# tPen.net
KiCad netlist of a schematic drawn in Altium Designer
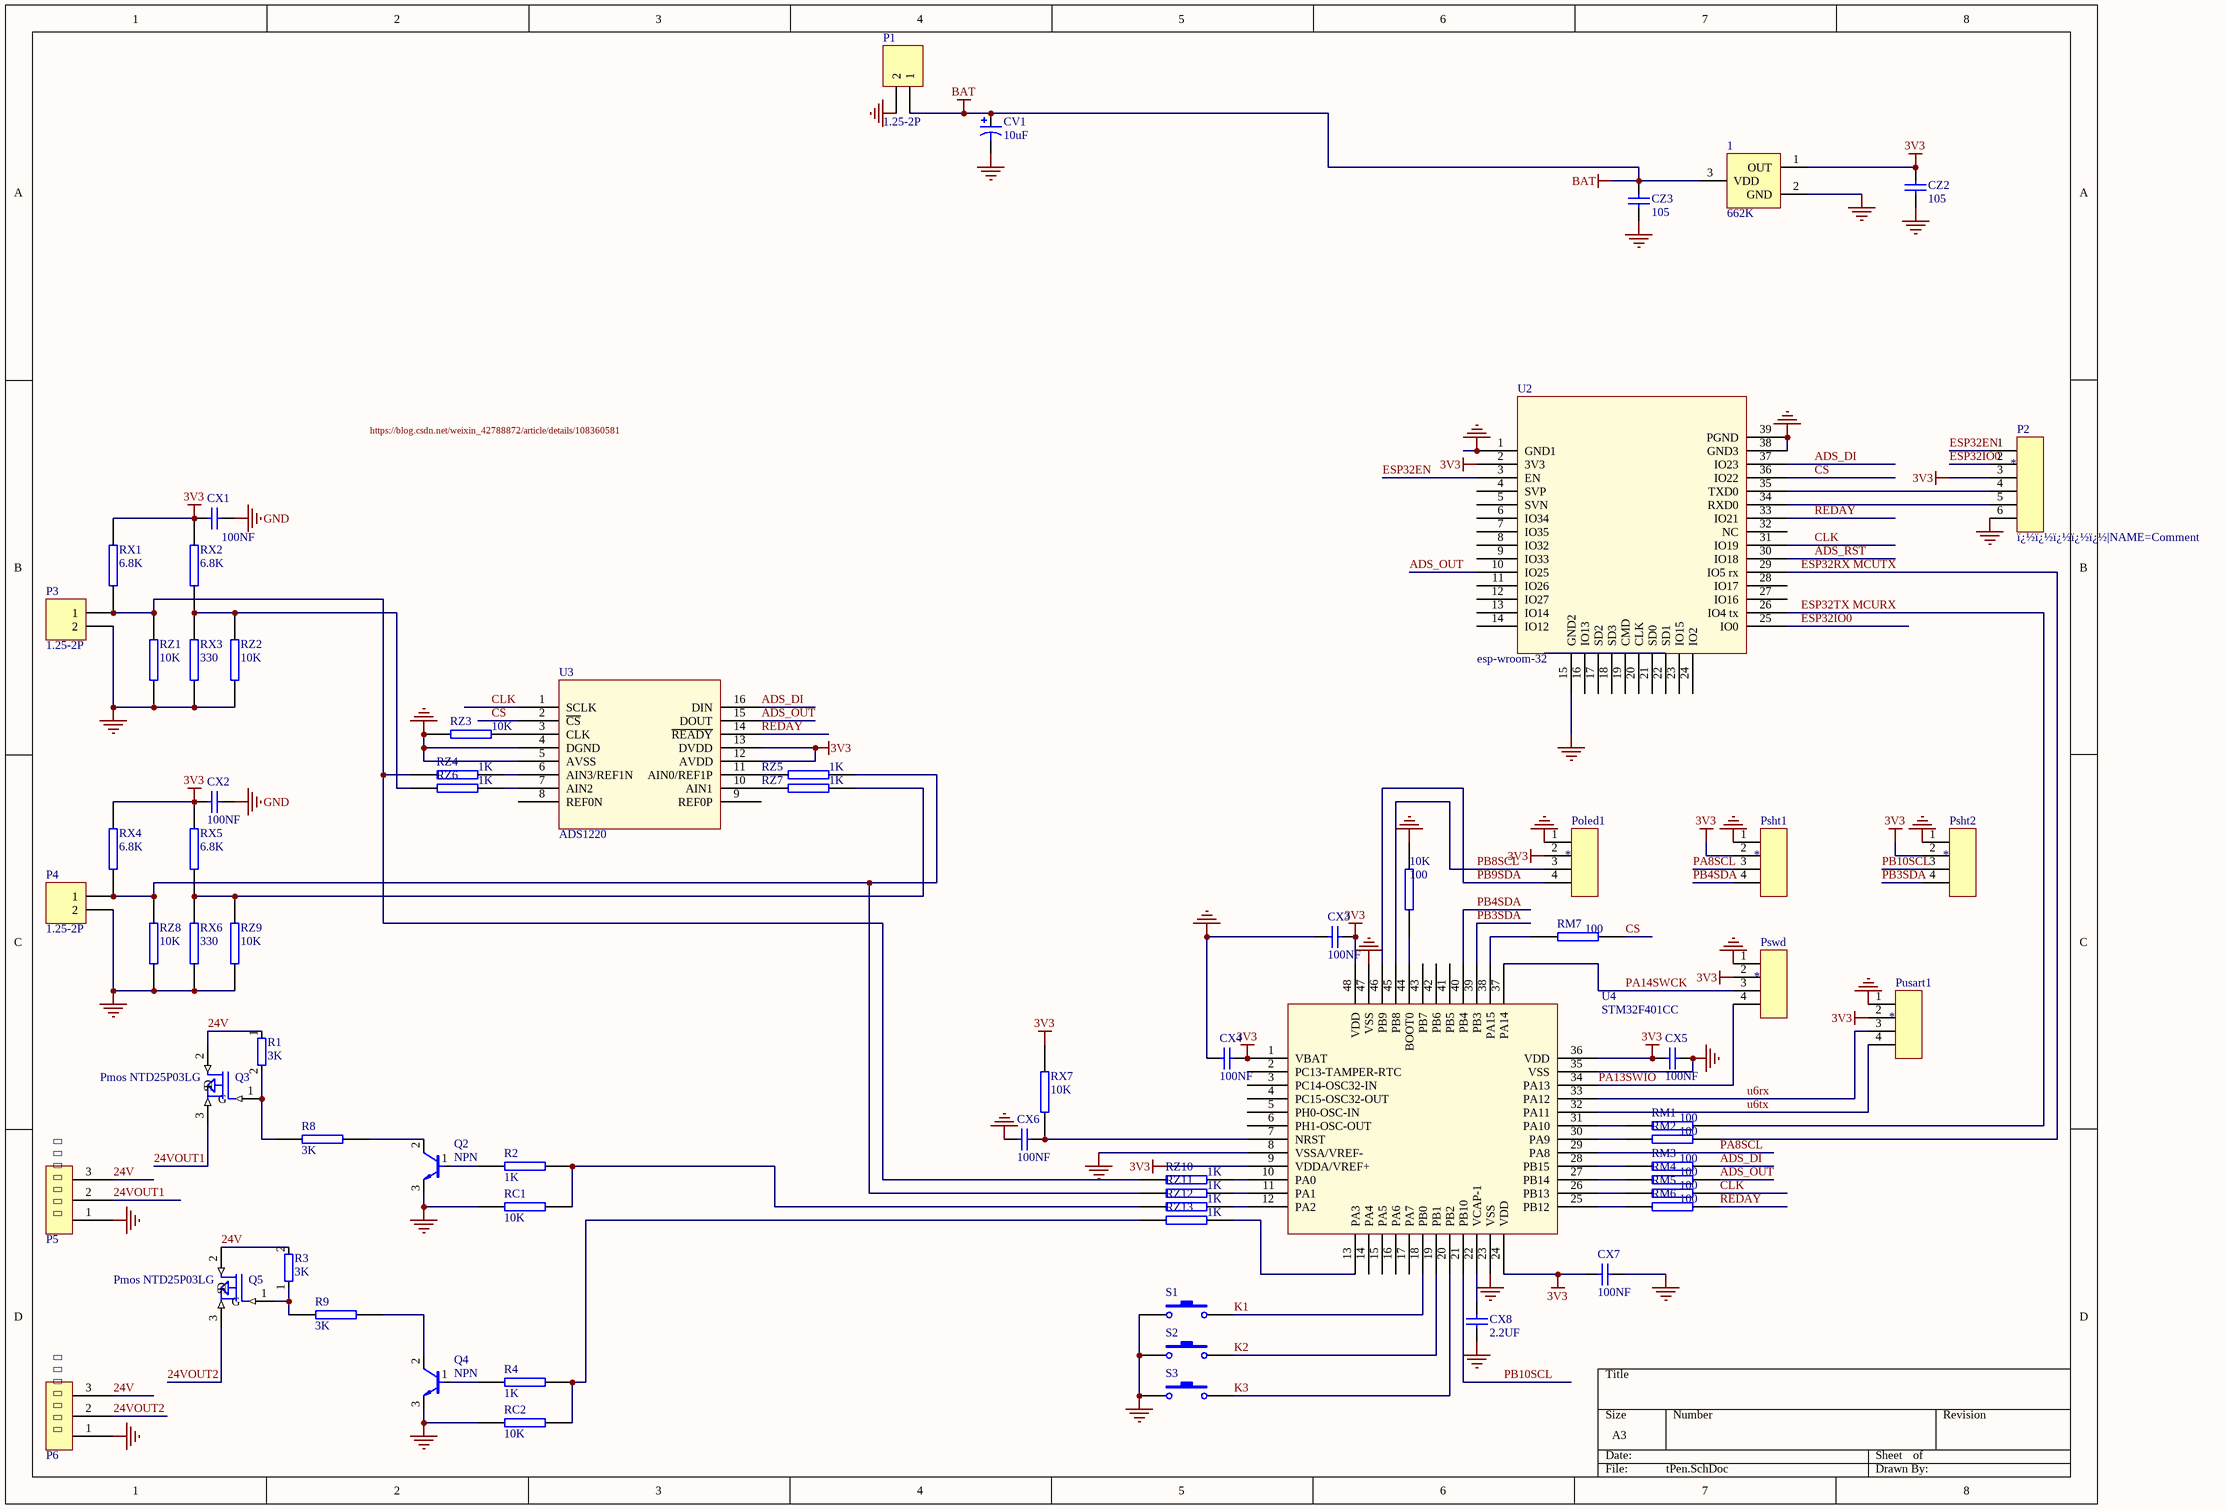
[diagram p0: tPen.SchDoc]

(export (version "E")
  (design (tool "Eeschema 10.0.6"))
  (components
    (comp (ref "1")
      (value "662K")
      (footprint "SOT23-3-1")
      (libsource (lib "SCHÔ­ï¿½ï¿½Í¼ï¿½ï¿½") (part "MH5330"))
    )
    (comp (ref "10K") (value "100") (footprint "0603") (libsource (lib "*") (part "RES2")))
    (comp (ref "CV1")
      (value "10uF")
      (footprint "0603")
      (description "Polarized Capacitor (Radial)")
      (libsource (lib "Miscellaneous Devices") (part "Cap Pol1"))
    )
    (comp (ref "CX1")
      (value "100NF")
      (footprint "0603")
      (description "Capacitor")
      (libsource (lib "Ô­ï¿½ï¿½Í¼ï¿½ï¿½") (part "104"))
    )
    (comp (ref "CX2")
      (value "100NF")
      (footprint "0603")
      (description "Capacitor")
      (libsource (lib "Ô­ï¿½ï¿½Í¼ï¿½ï¿½") (part "104"))
    )
    (comp (ref "CX3")
      (value "100NF")
      (footprint "0603")
      (description "Capacitor")
      (libsource (lib "Ô­ï¿½ï¿½Í¼ï¿½ï¿½") (part "104"))
    )
    (comp (ref "CX4")
      (value "100NF")
      (footprint "0603")
      (description "Capacitor")
      (libsource (lib "Ô­ï¿½ï¿½Í¼ï¿½ï¿½") (part "104"))
    )
    (comp (ref "CX5")
      (value "100NF")
      (footprint "0603")
      (description "Capacitor")
      (libsource (lib "Ô­ï¿½ï¿½Í¼ï¿½ï¿½") (part "104"))
    )
    (comp (ref "CX6")
      (value "100NF")
      (footprint "0603")
      (description "Capacitor")
      (libsource (lib "Ô­ï¿½ï¿½Í¼ï¿½ï¿½") (part "104"))
    )
    (comp (ref "CX7")
      (value "100NF")
      (footprint "0603")
      (description "Capacitor")
      (libsource (lib "Ô­ï¿½ï¿½Í¼ï¿½ï¿½") (part "104"))
    )
    (comp (ref "CX8")
      (value "2.2UF")
      (footprint "0603")
      (description "Capacitor")
      (libsource (lib "Ô­ï¿½ï¿½Í¼ï¿½ï¿½") (part "104"))
    )
    (comp (ref "CZ2")
      (value "105")
      (footprint "0603")
      (description "Capacitor")
      (libsource (lib "Ô­ï¿½ï¿½Í¼ï¿½ï¿½") (part "104"))
    )
    (comp (ref "CZ3")
      (value "105")
      (footprint "0603")
      (description "Capacitor")
      (libsource (lib "Ô­ï¿½ï¿½Í¼ï¿½ï¿½") (part "104"))
    )
    (comp (ref "P1")
      (value "1.25-2P")
      (footprint "1.25ï¿½ï¿½ï¿½ï¿½-ï¿½ï¿½Ê½Í¨ï¿½ï¿½-2P")
      (description "Header, 2-Pin")
      (fields (field (name "PUBLISHER") "Altium Limited"))
      (libsource (lib "") (part "Header 2_1"))
    )
    (comp (ref "P2")
      (value "*")
      (footprint "B6B-XH-A")
      (fields (field (name "ALTIUM_UNNAMED_1") "ï¿½ï¿½ï¿½ï¿½ï¿½NAME=Comment"))
      (libsource (lib "") (part "ï¿½Ó²ï¿½ï¿½ï¿½ï¿?P_1"))
    )
    (comp (ref "P3")
      (value "1.25-2P")
      (footprint "1.25ï¿½ï¿½ï¿½ï¿½-ï¿½ï¿½Ê½Í¨ï¿½ï¿½-2P")
      (description "Header, 2-Pin")
      (fields (field (name "PUBLISHER") "Altium Limited"))
      (libsource (lib "SCHÔ­ï¿½ï¿½Í¼ï¿½ï¿½") (part "Header 2"))
    )
    (comp (ref "P4")
      (value "1.25-2P")
      (footprint "1.25ï¿½ï¿½ï¿½ï¿½-ï¿½ï¿½Ê½Í¨ï¿½ï¿½-2P")
      (description "Header, 2-Pin")
      (fields (field (name "PUBLISHER") "Altium Limited"))
      (libsource (lib "SCHÔ­ï¿½ï¿½Í¼ï¿½ï¿½") (part "Header 2"))
    )
    (comp (ref "P5")
      (value "3Pï¿½ï¿½ï¿½ß¶ï¿½ï¿½ï¿½")
      (footprint "XH2.54-3")
      (libsource (lib "ï¿½Ó²ï¿½ï¿½Ôªï¿½ï¿½ï¿½ï¿?SchLib") (part "3Pï¿½ï¿½ï¿½ß¶ï¿½ï¿½ï¿½"))
    )
    (comp (ref "P6")
      (value "3Pï¿½ï¿½ï¿½ß¶ï¿½ï¿½ï¿½")
      (footprint "XH2.54-3")
      (libsource (lib "ï¿½Ó²ï¿½ï¿½Ôªï¿½ï¿½ï¿½ï¿?SchLib") (part "3Pï¿½ï¿½ï¿½ß¶ï¿½ï¿½ï¿½"))
    )
    (comp (ref "Poled1")
      (value "*")
      (footprint "0.96OLED")
      (libsource (lib "ï¿½Ó²ï¿½ï¿½Ôªï¿½ï¿½ï¿½ï¿?SchLib") (part "ï¿½Ó²ï¿½ï¿½ï¿½ï¿?P"))
    )
    (comp (ref "Psht1")
      (value "*")
      (footprint "B4B-XH-A")
      (libsource (lib "ï¿½Ó²ï¿½ï¿½Ôªï¿½ï¿½ï¿½ï¿?SchLib") (part "ï¿½Ó²ï¿½ï¿½ï¿½ï¿?P"))
    )
    (comp (ref "Psht2")
      (value "*")
      (footprint "B4B-XH-A")
      (libsource (lib "ï¿½Ó²ï¿½ï¿½Ôªï¿½ï¿½ï¿½ï¿?SchLib") (part "ï¿½Ó²ï¿½ï¿½ï¿½ï¿?P"))
    )
    (comp (ref "Pswd")
      (value "*")
      (footprint "B4B-XH-A")
      (libsource (lib "ï¿½Ó²ï¿½ï¿½Ôªï¿½ï¿½ï¿½ï¿?SchLib") (part "ï¿½Ó²ï¿½ï¿½ï¿½ï¿?P"))
    )
    (comp (ref "Pusart1")
      (value "*")
      (footprint "B4B-XH-A")
      (libsource (lib "ï¿½Ó²ï¿½ï¿½Ôªï¿½ï¿½ï¿½ï¿?SchLib") (part "ï¿½Ó²ï¿½ï¿½ï¿½ï¿?P"))
    )
    (comp (ref "Q2")
      (value "NPN")
      (footprint "SOT23")
      (libsource (lib "ï¿½ï¿½ï¿½ï¿½Ôªï¿½ï¿½ï¿½ï¿½") (part "NPN"))
    )
    (comp (ref "Q3")
      (value "Pmos NTD25P03LG")
      (libsource (lib "ï¿½ï¿½Ð§Ó¦ï¿½Ü¼ï¿½ï¿½É¿Ø¹ï¿½") (part "MOSFET P"))
    )
    (comp (ref "Q4")
      (value "NPN")
      (footprint "SOT23")
      (libsource (lib "ï¿½ï¿½ï¿½ï¿½Ôªï¿½ï¿½ï¿½ï¿½") (part "NPN"))
    )
    (comp (ref "Q5")
      (value "Pmos NTD25P03LG")
      (libsource (lib "ï¿½ï¿½Ð§Ó¦ï¿½Ü¼ï¿½ï¿½É¿Ø¹ï¿½") (part "MOSFET P"))
    )
    (comp (ref "R1") (value "3K") (footprint "0603") (libsource (lib "*") (part "RES")))
    (comp (ref "R2") (value "1K") (footprint "0603") (libsource (lib "*") (part "RES2")))
    (comp (ref "R3") (value "3K") (footprint "0603") (libsource (lib "*") (part "RES")))
    (comp (ref "R4") (value "1K") (footprint "0603") (libsource (lib "*") (part "RES2")))
    (comp (ref "R8") (value "3K") (footprint "0603") (libsource (lib "*") (part "RES2")))
    (comp (ref "R9") (value "3K") (footprint "0603") (libsource (lib "*") (part "RES2")))
    (comp (ref "RC1") (value "10K") (footprint "0603") (libsource (lib "*") (part "RES2")))
    (comp (ref "RC2") (value "10K") (footprint "0603") (libsource (lib "*") (part "RES2")))
    (comp (ref "RM1") (value "100") (footprint "0603") (libsource (lib "*") (part "RES2")))
    (comp (ref "RM2") (value "100") (footprint "0603") (libsource (lib "*") (part "RES2")))
    (comp (ref "RM3") (value "100") (footprint "0603") (libsource (lib "*") (part "RES2")))
    (comp (ref "RM4") (value "100") (footprint "0603") (libsource (lib "*") (part "RES2")))
    (comp (ref "RM5") (value "100") (footprint "0603") (libsource (lib "*") (part "RES2")))
    (comp (ref "RM6") (value "100") (footprint "0603") (libsource (lib "*") (part "RES2")))
    (comp (ref "RM7") (value "100") (footprint "0603") (libsource (lib "*") (part "RES2")))
    (comp (ref "RX1") (value "6.8K") (footprint "0603") (libsource (lib "*") (part "RES2")))
    (comp (ref "RX2") (value "6.8K") (footprint "0603") (libsource (lib "*") (part "RES2")))
    (comp (ref "RX3") (value "330") (footprint "0603") (libsource (lib "*") (part "RES2")))
    (comp (ref "RX4") (value "6.8K") (footprint "0603") (libsource (lib "*") (part "RES2")))
    (comp (ref "RX5") (value "6.8K") (footprint "0603") (libsource (lib "*") (part "RES2")))
    (comp (ref "RX6") (value "330") (footprint "0603") (libsource (lib "*") (part "RES2")))
    (comp (ref "RX7") (value "10K") (footprint "0603") (libsource (lib "*") (part "RES2")))
    (comp (ref "RZ1") (value "10K") (footprint "0603") (libsource (lib "*") (part "RES2")))
    (comp (ref "RZ2") (value "10K") (footprint "0603") (libsource (lib "*") (part "RES2")))
    (comp (ref "RZ3") (value "10K") (footprint "0603") (libsource (lib "*") (part "RES2")))
    (comp (ref "RZ4") (value "1K") (footprint "0603") (libsource (lib "*") (part "RES2")))
    (comp (ref "RZ5") (value "1K") (footprint "0603") (libsource (lib "*") (part "RES2")))
    (comp (ref "RZ6") (value "1K") (footprint "0603") (libsource (lib "*") (part "RES2")))
    (comp (ref "RZ7") (value "1K") (footprint "0603") (libsource (lib "*") (part "RES2")))
    (comp (ref "RZ8") (value "10K") (footprint "0603") (libsource (lib "*") (part "RES2")))
    (comp (ref "RZ9") (value "10K") (footprint "0603") (libsource (lib "*") (part "RES2")))
    (comp (ref "RZ10") (value "1K") (footprint "0603") (libsource (lib "*") (part "RES2")))
    (comp (ref "RZ11") (value "1K") (footprint "0603") (libsource (lib "*") (part "RES2")))
    (comp (ref "RZ12") (value "1K") (footprint "0603") (libsource (lib "*") (part "RES2")))
    (comp (ref "RZ13") (value "1K") (footprint "0603") (libsource (lib "*") (part "RES2")))
    (comp (ref "S1")
      (value "~")
      (footprint "ï¿½ï¿½Î»ï¿½ï¿½ï¿½ï¿½")
      (libsource (lib "ï¿½ï¿½ï¿½ï¿½_ï¿½ï¿½ï¿½ï¿½Ô­ï¿½ï¿½Í¼ï¿½ï¿½") (part "ï¿½á´¥ï¿½ï¿½ï¿½ï¿½"))
    )
    (comp (ref "S2")
      (value "~")
      (footprint "ï¿½ï¿½Î»ï¿½ï¿½ï¿½ï¿½")
      (libsource (lib "ï¿½ï¿½ï¿½ï¿½_ï¿½ï¿½ï¿½ï¿½Ô­ï¿½ï¿½Í¼ï¿½ï¿½") (part "ï¿½á´¥ï¿½ï¿½ï¿½ï¿½"))
    )
    (comp (ref "S3")
      (value "~")
      (footprint "ï¿½ï¿½Î»ï¿½ï¿½ï¿½ï¿½")
      (libsource (lib "ï¿½ï¿½ï¿½ï¿½_ï¿½ï¿½ï¿½ï¿½Ô­ï¿½ï¿½Í¼ï¿½ï¿½") (part "ï¿½á´¥ï¿½ï¿½ï¿½ï¿½"))
    )
    (comp (ref "U2")
      (value "esp-wroom-32")
      (footprint "ESP32")
      (libsource (lib "STM32F401CC") (part "esp-wroom-32"))
    )
    (comp (ref "U3") (value "ADS1220") (footprint "SSOP16") (libsource (lib "STM32F401CC") (part "ADS1220")))
    (comp (ref "U4")
      (value "STM32F401CC")
      (footprint "STM32F401CC-UFQFPN48")
      (libsource (lib "STM32F401CC") (part "STM32F401CC"))
    )
  )
  (nets
    (net (code "1") (name "/24V") (class "Default")
      (node (ref "P5") (pin "3") (pinfunction "3_3") (pintype "passive"))
      (node (ref "P6") (pin "3") (pinfunction "3_3") (pintype "passive"))
      (node (ref "Q3") (pin "2") (pinfunction "D_2") (pintype "input"))
      (node (ref "Q5") (pin "2") (pinfunction "D_2") (pintype "input"))
      (node (ref "R1") (pin "1") (pinfunction "1_1") (pintype "passive"))
      (node (ref "R3") (pin "2") (pinfunction "2_2") (pintype "passive"))
    )
    (net (code "2") (name "/24VOUT1") (class "Default")
      (node (ref "P5") (pin "2") (pinfunction "2_2") (pintype "passive"))
      (node (ref "Q3") (pin "3") (pinfunction "S_3") (pintype "input"))
    )
    (net (code "3") (name "/24VOUT2") (class "Default")
      (node (ref "P6") (pin "2") (pinfunction "2_2") (pintype "passive"))
      (node (ref "Q5") (pin "3") (pinfunction "S_3") (pintype "input"))
    )
    (net (code "4") (name "/ADS_DI") (class "Default")
      (node (ref "RM3") (pin "2") (pinfunction "2_2") (pintype "passive"))
      (node (ref "U2") (pin "37") (pinfunction "IO23_37") (pintype "passive"))
      (node (ref "U3") (pin "16") (pinfunction "DIN_16") (pintype "passive"))
    )
    (net (code "5") (name "/ADS_OUT") (class "Default")
      (node (ref "RM4") (pin "2") (pinfunction "2_2") (pintype "passive"))
      (node (ref "U2") (pin "10") (pinfunction "IO25_10") (pintype "passive"))
      (node (ref "U3") (pin "15") (pinfunction "DOUT_15") (pintype "passive"))
    )
    (net (code "6") (name "/ADS_RST") (class "Default")
      (node (ref "U2") (pin "30") (pinfunction "IO18_30") (pintype "passive"))
    )
    (net (code "7") (name "/CLK") (class "Default")
      (node (ref "RM5") (pin "2") (pinfunction "2_2") (pintype "passive"))
      (node (ref "U2") (pin "31") (pinfunction "IO19_31") (pintype "passive"))
      (node (ref "U3") (pin "1") (pinfunction "SCLK_1") (pintype "passive"))
    )
    (net (code "8") (name "/CS") (class "Default")
      (node (ref "RM7") (pin "2") (pinfunction "2_2") (pintype "passive"))
      (node (ref "U2") (pin "36") (pinfunction "IO22_36") (pintype "passive"))
      (node (ref "U3") (pin "2") (pinfunction "~{CS}_2") (pintype "passive"))
    )
    (net (code "9") (name "/ESP32EN") (class "Default")
      (node (ref "P2") (pin "1") (pinfunction "1_1") (pintype "passive"))
      (node (ref "U2") (pin "3") (pinfunction "EN_3") (pintype "passive"))
    )
    (net (code "10") (name "/ESP32IO0") (class "Default")
      (node (ref "P2") (pin "2") (pinfunction "2_2") (pintype "passive"))
      (node (ref "U2") (pin "25") (pinfunction "IO0_25") (pintype "passive"))
    )
    (net (code "11") (name "/ESP32RX MCUTX") (class "Default")
      (node (ref "RM2") (pin "2") (pinfunction "2_2") (pintype "passive"))
      (node (ref "U2") (pin "29") (pinfunction "IO5_rx_29") (pintype "passive"))
    )
    (net (code "12") (name "/ESP32TX MCURX") (class "Default")
      (node (ref "RM1") (pin "2") (pinfunction "2_2") (pintype "passive"))
      (node (ref "U2") (pin "26") (pinfunction "IO4_tx_26") (pintype "passive"))
    )
    (net (code "13") (name "/K1") (class "Default")
      (node (ref "S1") (pin "2") (pinfunction "2_2") (pintype "passive"))
      (node (ref "U4") (pin "18") (pinfunction "PB0_18") (pintype "passive"))
    )
    (net (code "14") (name "/K2") (class "Default")
      (node (ref "S2") (pin "2") (pinfunction "2_2") (pintype "passive"))
      (node (ref "U4") (pin "19") (pinfunction "PB1_19") (pintype "passive"))
    )
    (net (code "15") (name "/K3") (class "Default")
      (node (ref "S3") (pin "2") (pinfunction "2_2") (pintype "passive"))
      (node (ref "U4") (pin "20") (pinfunction "PB2_20") (pintype "passive"))
    )
    (net (code "16") (name "/PA8SCL") (class "Default")
      (node (ref "Psht1") (pin "3") (pinfunction "3_3") (pintype "passive"))
      (node (ref "U4") (pin "29") (pinfunction "PA8_29") (pintype "passive"))
    )
    (net (code "17") (name "/PA13SWIO") (class "Default")
      (node (ref "Pswd") (pin "4") (pinfunction "4_4") (pintype "passive"))
      (node (ref "U4") (pin "34") (pinfunction "PA13_34") (pintype "passive"))
    )
    (net (code "18") (name "/PA14SWCK") (class "Default")
      (node (ref "Pswd") (pin "3") (pinfunction "3_3") (pintype "passive"))
      (node (ref "U4") (pin "37") (pinfunction "PA14_37") (pintype "passive"))
    )
    (net (code "19") (name "/PB3SDA") (class "Default")
      (node (ref "Psht2") (pin "4") (pinfunction "4_4") (pintype "passive"))
      (node (ref "U4") (pin "39") (pinfunction "PB3_39") (pintype "passive"))
    )
    (net (code "20") (name "/PB4SDA") (class "Default")
      (node (ref "Psht1") (pin "4") (pinfunction "4_4") (pintype "passive"))
      (node (ref "U4") (pin "40") (pinfunction "PB4_40") (pintype "passive"))
    )
    (net (code "21") (name "/PB8SCL") (class "Default")
      (node (ref "Poled1") (pin "3") (pinfunction "3_3") (pintype "passive"))
      (node (ref "U4") (pin "45") (pinfunction "PB8_45") (pintype "passive"))
    )
    (net (code "22") (name "/PB9SDA") (class "Default")
      (node (ref "Poled1") (pin "4") (pinfunction "4_4") (pintype "passive"))
      (node (ref "U4") (pin "46") (pinfunction "PB9_46") (pintype "passive"))
    )
    (net (code "23") (name "/PB10SCL") (class "Default")
      (node (ref "Psht2") (pin "3") (pinfunction "3_3") (pintype "passive"))
      (node (ref "U4") (pin "21") (pinfunction "PB10_21") (pintype "passive"))
    )
    (net (code "24") (name "/REDAY") (class "Default")
      (node (ref "RM6") (pin "2") (pinfunction "2_2") (pintype "passive"))
      (node (ref "U2") (pin "33") (pinfunction "IO21_33") (pintype "passive"))
      (node (ref "U3") (pin "14") (pinfunction "~{READY}_14") (pintype "passive"))
    )
    (net (code "26") (name "/u6rx") (class "Default")
      (node (ref "Pusart1") (pin "3") (pinfunction "3_3") (pintype "passive"))
      (node (ref "U4") (pin "33") (pinfunction "PA12_33") (pintype "passive"))
    )
    (net (code "27") (name "/u6tx") (class "Default")
      (node (ref "Pusart1") (pin "4") (pinfunction "4_4") (pintype "passive"))
      (node (ref "U4") (pin "32") (pinfunction "PA11_32") (pintype "passive"))
    )
    (net (code "28") (name "3V3") (class "Default")
      (node (ref "1") (pin "1") (pinfunction "OUT_1") (pintype "passive"))
      (node (ref "CX1") (pin "1") (pinfunction "1_1") (pintype "passive"))
      (node (ref "CX2") (pin "1") (pinfunction "1_1") (pintype "passive"))
      (node (ref "CX3") (pin "2") (pinfunction "2_2") (pintype "passive"))
      (node (ref "CX4") (pin "2") (pinfunction "2_2") (pintype "passive"))
      (node (ref "CX5") (pin "1") (pinfunction "1_1") (pintype "passive"))
      (node (ref "CX7") (pin "1") (pinfunction "1_1") (pintype "passive"))
      (node (ref "CZ2") (pin "1") (pinfunction "1_1") (pintype "passive"))
      (node (ref "P2") (pin "3") (pinfunction "3_3") (pintype "passive"))
      (node (ref "Poled1") (pin "2") (pinfunction "2_2") (pintype "passive"))
      (node (ref "Psht1") (pin "2") (pinfunction "2_2") (pintype "passive"))
      (node (ref "Psht2") (pin "2") (pinfunction "2_2") (pintype "passive"))
      (node (ref "Pswd") (pin "2") (pinfunction "2_2") (pintype "passive"))
      (node (ref "Pusart1") (pin "2") (pinfunction "2_2") (pintype "passive"))
      (node (ref "RX1") (pin "1") (pinfunction "1_1") (pintype "passive"))
      (node (ref "RX2") (pin "1") (pinfunction "1_1") (pintype "passive"))
      (node (ref "RX4") (pin "1") (pinfunction "1_1") (pintype "passive"))
      (node (ref "RX5") (pin "1") (pinfunction "1_1") (pintype "passive"))
      (node (ref "RX7") (pin "2") (pinfunction "2_2") (pintype "passive"))
      (node (ref "U2") (pin "2") (pinfunction "3V3_2") (pintype "passive"))
      (node (ref "U3") (pin "12") (pinfunction "AVDD_12") (pintype "passive"))
      (node (ref "U3") (pin "13") (pinfunction "DVDD_13") (pintype "passive"))
      (node (ref "U4") (pin "1") (pinfunction "VBAT_1") (pintype "passive"))
      (node (ref "U4") (pin "24") (pinfunction "VDD_24") (pintype "passive"))
      (node (ref "U4") (pin "36") (pinfunction "VDD_36") (pintype "passive"))
      (node (ref "U4") (pin "48") (pinfunction "VDD_48") (pintype "passive"))
      (node (ref "U4") (pin "9") (pinfunction "VDDA/VREF+_9") (pintype "passive"))
    )
    (net (code "29") (name "BAT") (class "Default")
      (node (ref "1") (pin "3") (pinfunction "VDD_3") (pintype "passive"))
      (node (ref "CV1") (pin "1") (pinfunction "1_1") (pintype "passive"))
      (node (ref "CZ3") (pin "1") (pinfunction "1_1") (pintype "passive"))
      (node (ref "P1") (pin "1") (pinfunction "1_1") (pintype "passive"))
    )
    (net (code "30") (name "GND") (class "Default")
      (node (ref "1") (pin "2") (pinfunction "GND_2") (pintype "passive"))
      (node (ref "10K") (pin "2") (pinfunction "2_2") (pintype "passive"))
      (node (ref "CV1") (pin "2") (pinfunction "2_2") (pintype "passive"))
      (node (ref "CX1") (pin "2") (pinfunction "2_2") (pintype "passive"))
      (node (ref "CX2") (pin "2") (pinfunction "2_2") (pintype "passive"))
      (node (ref "CX3") (pin "1") (pinfunction "1_1") (pintype "passive"))
      (node (ref "CX4") (pin "1") (pinfunction "1_1") (pintype "passive"))
      (node (ref "CX5") (pin "2") (pinfunction "2_2") (pintype "passive"))
      (node (ref "CX6") (pin "2") (pinfunction "2_2") (pintype "passive"))
      (node (ref "CX7") (pin "2") (pinfunction "2_2") (pintype "passive"))
      (node (ref "CX8") (pin "2") (pinfunction "2_2") (pintype "passive"))
      (node (ref "CZ2") (pin "2") (pinfunction "2_2") (pintype "passive"))
      (node (ref "CZ3") (pin "2") (pinfunction "2_2") (pintype "passive"))
      (node (ref "P1") (pin "2") (pinfunction "2_2") (pintype "passive"))
      (node (ref "P2") (pin "6") (pinfunction "6_6") (pintype "passive"))
      (node (ref "P3") (pin "2") (pinfunction "2_2") (pintype "passive"))
      (node (ref "P4") (pin "2") (pinfunction "2_2") (pintype "passive"))
      (node (ref "P5") (pin "1") (pinfunction "1_1") (pintype "passive"))
      (node (ref "P6") (pin "1") (pinfunction "1_1") (pintype "passive"))
      (node (ref "Poled1") (pin "1") (pinfunction "1_1") (pintype "passive"))
      (node (ref "Psht1") (pin "1") (pinfunction "1_1") (pintype "passive"))
      (node (ref "Psht2") (pin "1") (pinfunction "1_1") (pintype "passive"))
      (node (ref "Pswd") (pin "1") (pinfunction "1_1") (pintype "passive"))
      (node (ref "Pusart1") (pin "1") (pinfunction "1_1") (pintype "passive"))
      (node (ref "Q2") (pin "3") (pinfunction "3e_3") (pintype "passive"))
      (node (ref "Q4") (pin "3") (pinfunction "3e_3") (pintype "passive"))
      (node (ref "RC1") (pin "1") (pinfunction "1_1") (pintype "passive"))
      (node (ref "RC2") (pin "1") (pinfunction "1_1") (pintype "passive"))
      (node (ref "RX3") (pin "2") (pinfunction "2_2") (pintype "passive"))
      (node (ref "RX6") (pin "2") (pinfunction "2_2") (pintype "passive"))
      (node (ref "RZ1") (pin "2") (pinfunction "2_2") (pintype "passive"))
      (node (ref "RZ2") (pin "2") (pinfunction "2_2") (pintype "passive"))
      (node (ref "RZ3") (pin "1") (pinfunction "1_1") (pintype "passive"))
      (node (ref "RZ8") (pin "2") (pinfunction "2_2") (pintype "passive"))
      (node (ref "RZ9") (pin "2") (pinfunction "2_2") (pintype "passive"))
      (node (ref "S1") (pin "1") (pinfunction "1_1") (pintype "passive"))
      (node (ref "S2") (pin "1") (pinfunction "1_1") (pintype "passive"))
      (node (ref "S3") (pin "1") (pinfunction "1_1") (pintype "passive"))
      (node (ref "U2") (pin "1") (pinfunction "GND1_1") (pintype "passive"))
      (node (ref "U2") (pin "15") (pinfunction "GND2_15") (pintype "passive"))
      (node (ref "U2") (pin "38") (pinfunction "GND3_38") (pintype "passive"))
      (node (ref "U2") (pin "39") (pinfunction "PGND_39") (pintype "passive"))
      (node (ref "U3") (pin "4") (pinfunction "DGND_4") (pintype "passive"))
      (node (ref "U3") (pin "5") (pinfunction "AVSS_5") (pintype "passive"))
      (node (ref "U4") (pin "23") (pinfunction "VSS_23") (pintype "passive"))
      (node (ref "U4") (pin "35") (pinfunction "VSS_35") (pintype "passive"))
      (node (ref "U4") (pin "47") (pinfunction "VSS_47") (pintype "passive"))
      (node (ref "U4") (pin "8") (pinfunction "VSSA/VREF-_8") (pintype "passive"))
    )
    (net (code "31") (name "Net-(P3-Pad1)") (class "Default")
      (node (ref "P3") (pin "1") (pinfunction "1_1") (pintype "passive"))
      (node (ref "RX1") (pin "2") (pinfunction "2_2") (pintype "passive"))
      (node (ref "RZ1") (pin "1") (pinfunction "1_1") (pintype "passive"))
      (node (ref "RZ10") (pin "1") (pinfunction "1_1") (pintype "passive"))
      (node (ref "RZ4") (pin "1") (pinfunction "1_1") (pintype "passive"))
    )
    (net (code "32") (name "Net-(P4-Pad1)") (class "Default")
      (node (ref "P4") (pin "1") (pinfunction "1_1") (pintype "passive"))
      (node (ref "RX4") (pin "2") (pinfunction "2_2") (pintype "passive"))
      (node (ref "RZ11") (pin "1") (pinfunction "1_1") (pintype "passive"))
      (node (ref "RZ5") (pin "2") (pinfunction "2_2") (pintype "passive"))
      (node (ref "RZ8") (pin "1") (pinfunction "1_1") (pintype "passive"))
    )
    (net (code "33") (name "Net-(Q2-1b)") (class "Default")
      (node (ref "Q2") (pin "1") (pinfunction "1b_1") (pintype "passive"))
      (node (ref "R2") (pin "1") (pinfunction "1_1") (pintype "passive"))
    )
    (net (code "34") (name "Net-(Q2-2c)") (class "Default")
      (node (ref "Q2") (pin "2") (pinfunction "2c_2") (pintype "passive"))
      (node (ref "R8") (pin "2") (pinfunction "2_2") (pintype "passive"))
    )
    (net (code "35") (name "Net-(Q3-G)") (class "Default")
      (node (ref "Q3") (pin "1") (pinfunction "G_1") (pintype "input"))
      (node (ref "R1") (pin "2") (pinfunction "2_2") (pintype "passive"))
      (node (ref "R8") (pin "1") (pinfunction "1_1") (pintype "passive"))
    )
    (net (code "36") (name "Net-(Q4-1b)") (class "Default")
      (node (ref "Q4") (pin "1") (pinfunction "1b_1") (pintype "passive"))
      (node (ref "R4") (pin "1") (pinfunction "1_1") (pintype "passive"))
    )
    (net (code "37") (name "Net-(Q4-2c)") (class "Default")
      (node (ref "Q4") (pin "2") (pinfunction "2c_2") (pintype "passive"))
      (node (ref "R9") (pin "2") (pinfunction "2_2") (pintype "passive"))
    )
    (net (code "38") (name "Net-(Q5-G)") (class "Default")
      (node (ref "Q5") (pin "1") (pinfunction "G_1") (pintype "input"))
      (node (ref "R3") (pin "1") (pinfunction "1_1") (pintype "passive"))
      (node (ref "R9") (pin "1") (pinfunction "1_1") (pintype "passive"))
    )
    (net (code "39") (name "Net-(R2-Pad2)") (class "Default")
      (node (ref "R2") (pin "2") (pinfunction "2_2") (pintype "passive"))
      (node (ref "RC1") (pin "2") (pinfunction "2_2") (pintype "passive"))
      (node (ref "RZ12") (pin "1") (pinfunction "1_1") (pintype "passive"))
    )
    (net (code "40") (name "Net-(R4-Pad2)") (class "Default")
      (node (ref "R4") (pin "2") (pinfunction "2_2") (pintype "passive"))
      (node (ref "RC2") (pin "2") (pinfunction "2_2") (pintype "passive"))
      (node (ref "RZ13") (pin "1") (pinfunction "1_1") (pintype "passive"))
    )
    (net (code "41") (name "Net-(RX2-Pad2)") (class "Default")
      (node (ref "RX2") (pin "2") (pinfunction "2_2") (pintype "passive"))
      (node (ref "RX3") (pin "1") (pinfunction "1_1") (pintype "passive"))
      (node (ref "RZ2") (pin "1") (pinfunction "1_1") (pintype "passive"))
      (node (ref "RZ6") (pin "1") (pinfunction "1_1") (pintype "passive"))
    )
    (net (code "42") (name "Net-(RX5-Pad2)") (class "Default")
      (node (ref "RX5") (pin "2") (pinfunction "2_2") (pintype "passive"))
      (node (ref "RX6") (pin "1") (pinfunction "1_1") (pintype "passive"))
      (node (ref "RZ7") (pin "2") (pinfunction "2_2") (pintype "passive"))
      (node (ref "RZ9") (pin "1") (pinfunction "1_1") (pintype "passive"))
    )
    (net (code "43") (name "Net-(U2-RXD0)") (class "Default")
      (node (ref "P2") (pin "5") (pinfunction "5_5") (pintype "passive"))
      (node (ref "U2") (pin "34") (pinfunction "RXD0_34") (pintype "passive"))
    )
    (net (code "44") (name "Net-(U2-TXD0)") (class "Default")
      (node (ref "P2") (pin "4") (pinfunction "4_4") (pintype "passive"))
      (node (ref "U2") (pin "35") (pinfunction "TXD0_35") (pintype "passive"))
    )
    (net (code "45") (name "Net-(U3-AIN0{slash}REF1P)") (class "Default")
      (node (ref "RZ5") (pin "1") (pinfunction "1_1") (pintype "passive"))
      (node (ref "U3") (pin "11") (pinfunction "AIN0/REF1P_11") (pintype "passive"))
    )
    (net (code "46") (name "Net-(U3-AIN1)") (class "Default")
      (node (ref "RZ7") (pin "1") (pinfunction "1_1") (pintype "passive"))
      (node (ref "U3") (pin "10") (pinfunction "AIN1_10") (pintype "passive"))
    )
    (net (code "47") (name "Net-(U3-AIN2)") (class "Default")
      (node (ref "RZ6") (pin "2") (pinfunction "2_2") (pintype "passive"))
      (node (ref "U3") (pin "7") (pinfunction "AIN2_7") (pintype "passive"))
    )
    (net (code "48") (name "Net-(U3-AIN3{slash}REF1N)") (class "Default")
      (node (ref "RZ4") (pin "2") (pinfunction "2_2") (pintype "passive"))
      (node (ref "U3") (pin "6") (pinfunction "AIN3/REF1N_6") (pintype "passive"))
    )
    (net (code "49") (name "Net-(U3-CLK)") (class "Default")
      (node (ref "RZ3") (pin "2") (pinfunction "2_2") (pintype "passive"))
      (node (ref "U3") (pin "3") (pinfunction "CLK_3") (pintype "passive"))
    )
    (net (code "50") (name "Net-(U4-BOOT0)") (class "Default")
      (node (ref "10K") (pin "1") (pinfunction "1_1") (pintype "passive"))
      (node (ref "U4") (pin "44") (pinfunction "BOOT0_44") (pintype "passive"))
    )
    (net (code "51") (name "Net-(U4-NRST)") (class "Default")
      (node (ref "CX6") (pin "1") (pinfunction "1_1") (pintype "passive"))
      (node (ref "RX7") (pin "1") (pinfunction "1_1") (pintype "passive"))
      (node (ref "U4") (pin "7") (pinfunction "NRST_7") (pintype "passive"))
    )
    (net (code "52") (name "Net-(U4-PA0)") (class "Default")
      (node (ref "RZ10") (pin "2") (pinfunction "2_2") (pintype "passive"))
      (node (ref "U4") (pin "10") (pinfunction "PA0_10") (pintype "passive"))
    )
    (net (code "53") (name "Net-(U4-PA1)") (class "Default")
      (node (ref "RZ11") (pin "2") (pinfunction "2_2") (pintype "passive"))
      (node (ref "U4") (pin "11") (pinfunction "PA1_11") (pintype "passive"))
    )
    (net (code "54") (name "Net-(U4-PA2)") (class "Default")
      (node (ref "RZ12") (pin "2") (pinfunction "2_2") (pintype "passive"))
      (node (ref "U4") (pin "12") (pinfunction "PA2_12") (pintype "passive"))
    )
    (net (code "55") (name "Net-(U4-PA3)") (class "Default")
      (node (ref "RZ13") (pin "2") (pinfunction "2_2") (pintype "passive"))
      (node (ref "U4") (pin "13") (pinfunction "PA3_13") (pintype "passive"))
    )
    (net (code "56") (name "Net-(U4-PA9)") (class "Default")
      (node (ref "RM2") (pin "1") (pinfunction "1_1") (pintype "passive"))
      (node (ref "U4") (pin "30") (pinfunction "PA9_30") (pintype "passive"))
    )
    (net (code "57") (name "Net-(U4-PA10)") (class "Default")
      (node (ref "RM1") (pin "1") (pinfunction "1_1") (pintype "passive"))
      (node (ref "U4") (pin "31") (pinfunction "PA10_31") (pintype "passive"))
    )
    (net (code "58") (name "Net-(U4-PA15)") (class "Default")
      (node (ref "RM7") (pin "1") (pinfunction "1_1") (pintype "passive"))
      (node (ref "U4") (pin "38") (pinfunction "PA15_38") (pintype "passive"))
    )
    (net (code "59") (name "Net-(U4-PB12)") (class "Default")
      (node (ref "RM6") (pin "1") (pinfunction "1_1") (pintype "passive"))
      (node (ref "U4") (pin "25") (pinfunction "PB12_25") (pintype "passive"))
    )
    (net (code "60") (name "Net-(U4-PB13)") (class "Default")
      (node (ref "RM5") (pin "1") (pinfunction "1_1") (pintype "passive"))
      (node (ref "U4") (pin "26") (pinfunction "PB13_26") (pintype "passive"))
    )
    (net (code "61") (name "Net-(U4-PB14)") (class "Default")
      (node (ref "RM4") (pin "1") (pinfunction "1_1") (pintype "passive"))
      (node (ref "U4") (pin "27") (pinfunction "PB14_27") (pintype "passive"))
    )
    (net (code "62") (name "Net-(U4-PB15)") (class "Default")
      (node (ref "RM3") (pin "1") (pinfunction "1_1") (pintype "passive"))
      (node (ref "U4") (pin "28") (pinfunction "PB15_28") (pintype "passive"))
    )
    (net (code "63") (name "Net-(U4-VCAP-1)") (class "Default")
      (node (ref "CX8") (pin "1") (pinfunction "1_1") (pintype "passive"))
      (node (ref "U4") (pin "22") (pinfunction "VCAP-1_22") (pintype "passive"))
    )
    (net (code "64") (name "unconnected-(U2-CLK-Pad20)") (class "Default")
      (node (ref "U2") (pin "20") (pinfunction "CLK_20") (pintype "passive"))
    )
    (net (code "65") (name "unconnected-(U2-CMD-Pad19)") (class "Default")
      (node (ref "U2") (pin "19") (pinfunction "CMD_19") (pintype "passive"))
    )
    (net (code "66") (name "unconnected-(U2-IO2-Pad24)") (class "Default")
      (node (ref "U2") (pin "24") (pinfunction "IO2_24") (pintype "passive"))
    )
    (net (code "67") (name "unconnected-(U2-IO12-Pad14)") (class "Default")
      (node (ref "U2") (pin "14") (pinfunction "IO12_14") (pintype "passive"))
    )
    (net (code "68") (name "unconnected-(U2-IO13-Pad16)") (class "Default")
      (node (ref "U2") (pin "16") (pinfunction "IO13_16") (pintype "passive"))
    )
    (net (code "69") (name "unconnected-(U2-IO14-Pad13)") (class "Default")
      (node (ref "U2") (pin "13") (pinfunction "IO14_13") (pintype "passive"))
    )
    (net (code "70") (name "unconnected-(U2-IO15-Pad23)") (class "Default")
      (node (ref "U2") (pin "23") (pinfunction "IO15_23") (pintype "passive"))
    )
    (net (code "71") (name "unconnected-(U2-IO16-Pad27)") (class "Default")
      (node (ref "U2") (pin "27") (pinfunction "IO16_27") (pintype "passive"))
    )
    (net (code "72") (name "unconnected-(U2-IO17-Pad28)") (class "Default")
      (node (ref "U2") (pin "28") (pinfunction "IO17_28") (pintype "passive"))
    )
    (net (code "73") (name "unconnected-(U2-IO26-Pad11)") (class "Default")
      (node (ref "U2") (pin "11") (pinfunction "IO26_11") (pintype "passive"))
    )
    (net (code "74") (name "unconnected-(U2-IO27-Pad12)") (class "Default")
      (node (ref "U2") (pin "12") (pinfunction "IO27_12") (pintype "passive"))
    )
    (net (code "75") (name "unconnected-(U2-IO32-Pad8)") (class "Default")
      (node (ref "U2") (pin "8") (pinfunction "IO32_8") (pintype "passive"))
    )
    (net (code "76") (name "unconnected-(U2-IO33-Pad9)") (class "Default")
      (node (ref "U2") (pin "9") (pinfunction "IO33_9") (pintype "passive"))
    )
    (net (code "77") (name "unconnected-(U2-IO34-Pad6)") (class "Default")
      (node (ref "U2") (pin "6") (pinfunction "IO34_6") (pintype "passive"))
    )
    (net (code "78") (name "unconnected-(U2-IO35-Pad7)") (class "Default")
      (node (ref "U2") (pin "7") (pinfunction "IO35_7") (pintype "passive"))
    )
    (net (code "79") (name "unconnected-(U2-NC-Pad32)") (class "Default")
      (node (ref "U2") (pin "32") (pinfunction "NC_32") (pintype "passive"))
    )
    (net (code "80") (name "unconnected-(U2-SD0-Pad21)") (class "Default")
      (node (ref "U2") (pin "21") (pinfunction "SD0_21") (pintype "passive"))
    )
    (net (code "81") (name "unconnected-(U2-SD1-Pad22)") (class "Default")
      (node (ref "U2") (pin "22") (pinfunction "SD1_22") (pintype "passive"))
    )
    (net (code "82") (name "unconnected-(U2-SD2-Pad17)") (class "Default")
      (node (ref "U2") (pin "17") (pinfunction "SD2_17") (pintype "passive"))
    )
    (net (code "83") (name "unconnected-(U2-SD3-Pad18)") (class "Default")
      (node (ref "U2") (pin "18") (pinfunction "SD3_18") (pintype "passive"))
    )
    (net (code "84") (name "unconnected-(U2-SVN-Pad5)") (class "Default")
      (node (ref "U2") (pin "5") (pinfunction "SVN_5") (pintype "passive"))
    )
    (net (code "85") (name "unconnected-(U2-SVP-Pad4)") (class "Default")
      (node (ref "U2") (pin "4") (pinfunction "SVP_4") (pintype "passive"))
    )
    (net (code "86") (name "unconnected-(U3-REF0N-Pad8)") (class "Default")
      (node (ref "U3") (pin "8") (pinfunction "REF0N_8") (pintype "passive"))
    )
    (net (code "87") (name "unconnected-(U3-REF0P-Pad9)") (class "Default")
      (node (ref "U3") (pin "9") (pinfunction "REF0P_9") (pintype "passive"))
    )
    (net (code "88") (name "unconnected-(U4-PA4-Pad14)") (class "Default")
      (node (ref "U4") (pin "14") (pinfunction "PA4_14") (pintype "passive"))
    )
    (net (code "89") (name "unconnected-(U4-PA5-Pad15)") (class "Default")
      (node (ref "U4") (pin "15") (pinfunction "PA5_15") (pintype "passive"))
    )
    (net (code "90") (name "unconnected-(U4-PA6-Pad16)") (class "Default")
      (node (ref "U4") (pin "16") (pinfunction "PA6_16") (pintype "passive"))
    )
    (net (code "91") (name "unconnected-(U4-PA7-Pad17)") (class "Default")
      (node (ref "U4") (pin "17") (pinfunction "PA7_17") (pintype "passive"))
    )
    (net (code "92") (name "unconnected-(U4-PB5-Pad41)") (class "Default")
      (node (ref "U4") (pin "41") (pinfunction "PB5_41") (pintype "passive"))
    )
    (net (code "93") (name "unconnected-(U4-PB6-Pad42)") (class "Default")
      (node (ref "U4") (pin "42") (pinfunction "PB6_42") (pintype "passive"))
    )
    (net (code "94") (name "unconnected-(U4-PB7-Pad43)") (class "Default")
      (node (ref "U4") (pin "43") (pinfunction "PB7_43") (pintype "passive"))
    )
    (net (code "95") (name "unconnected-(U4-PC13-TAMPER-RTC-Pad2)") (class "Default")
      (node (ref "U4") (pin "2") (pinfunction "PC13-TAMPER-RTC_2") (pintype "passive"))
    )
    (net (code "96") (name "unconnected-(U4-PC14-OSC32-IN-Pad3)") (class "Default")
      (node (ref "U4") (pin "3") (pinfunction "PC14-OSC32-IN_3") (pintype "passive"))
    )
    (net (code "97") (name "unconnected-(U4-PC15-OSC32-OUT-Pad4)") (class "Default")
      (node (ref "U4") (pin "4") (pinfunction "PC15-OSC32-OUT_4") (pintype "passive"))
    )
    (net (code "98") (name "unconnected-(U4-PH0-OSC-IN-Pad5)") (class "Default")
      (node (ref "U4") (pin "5") (pinfunction "PH0-OSC-IN_5") (pintype "passive"))
    )
    (net (code "99") (name "unconnected-(U4-PH1-OSC-OUT-Pad6)") (class "Default")
      (node (ref "U4") (pin "6") (pinfunction "PH1-OSC-OUT_6") (pintype "passive"))
    )
  )
)
